# Portier.net
KiCad netlist of a schematic drawn in Altium Designer
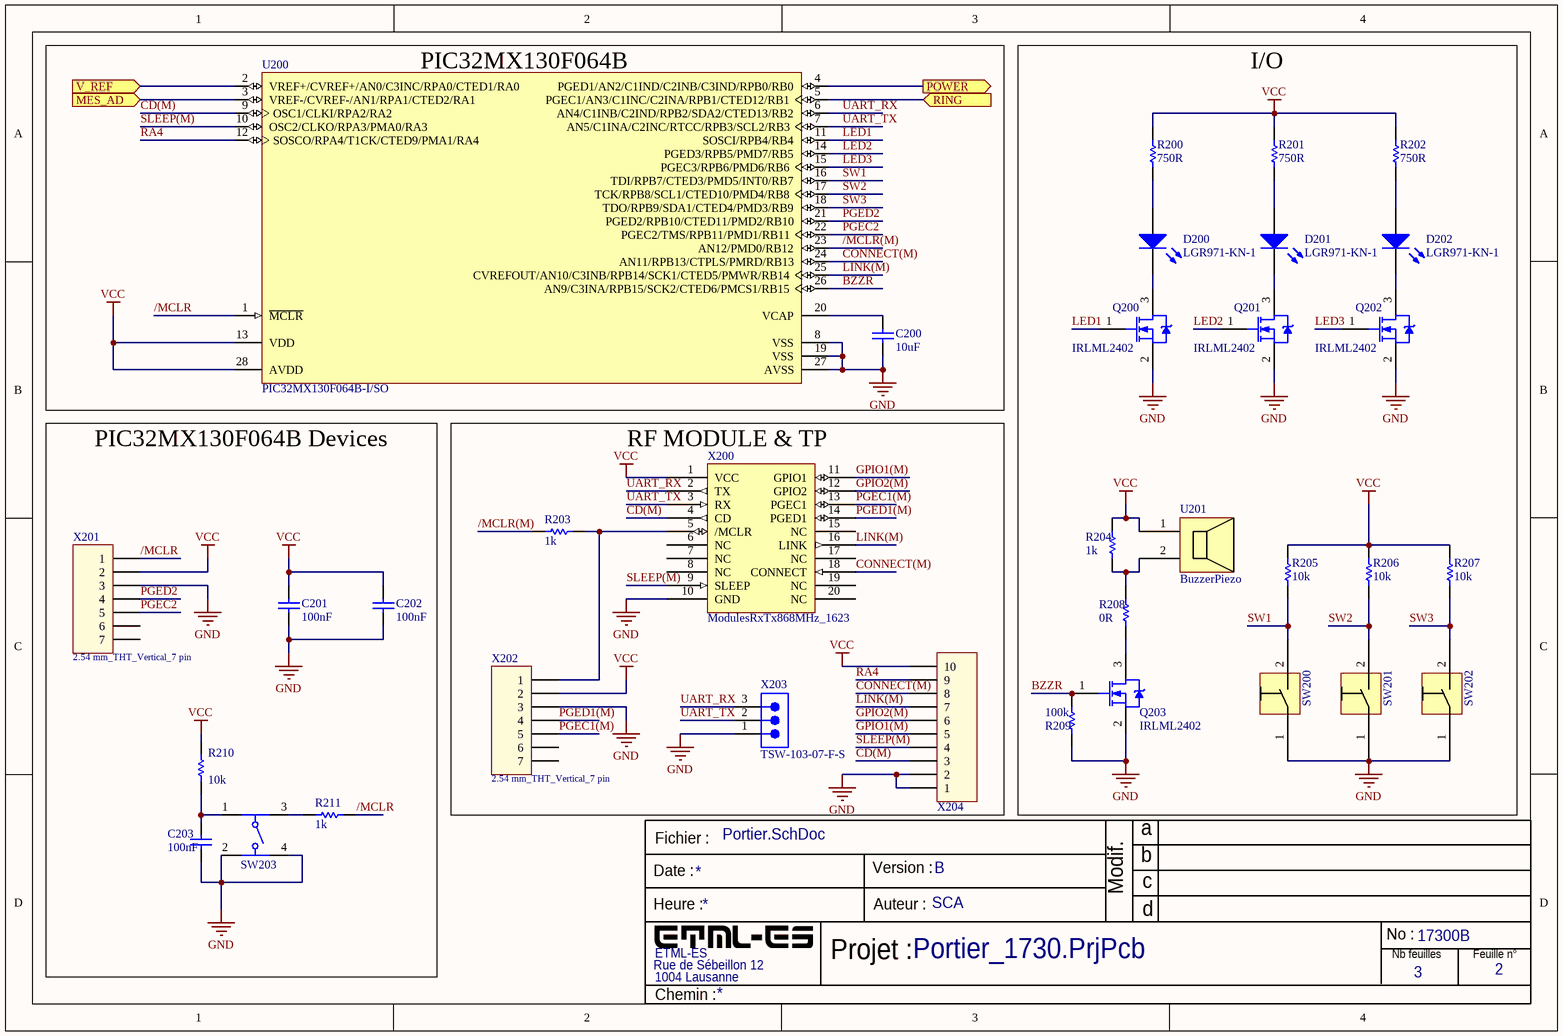
[diagram p0: Portier.SchDoc]

(export (version "E")
  (design (tool "Eeschema 10.0.6"))
  (components
    (comp (ref "C200")
      (value "10uF")
      (footprint "CAPC3216X180X50ML20T25")
      (description "CAP, Ceramic, 10 uF, +/- 10%, 16 V, -55 to 125 degC, 1206 (3216 Metric), RoHS, Tape and Reel")
      (libsource (lib "Altium Content Vault") (part "CMP-1664-00006-1"))
    )
    (comp (ref "C201")
      (value "100nF")
      (footprint "CAPC2013X100X20NL20")
      (description "Chip Capacitor, 100 nF, +/- 10%, 16 V, -55 to 85 degC, 0805 (2012 Metric), RoHS, Tape and Reel")
      (libsource (lib "Altium Content Vault") (part "CMP-1663-00007-1"))
    )
    (comp (ref "C202")
      (value "100nF")
      (footprint "CAPC2013X100X20NL20")
      (description "Chip Capacitor, 100 nF, +/- 10%, 16 V, -55 to 85 degC, 0805 (2012 Metric), RoHS, Tape and Reel")
      (libsource (lib "Altium Content Vault") (part "CMP-1663-00007-1"))
    )
    (comp (ref "C203")
      (value "100nF")
      (footprint "CAPC2013X100X20NL20")
      (description "Chip Capacitor, 100 nF, +/- 10%, 16 V, -55 to 85 degC, 0805 (2012 Metric), RoHS, Tape and Reel")
      (libsource (lib "Altium Content Vault") (part "CMP-1663-00007-1"))
    )
    (comp (ref "D200")
      (value "LGR971-KN-1")
      (footprint "LED_0805")
      (description "SMD mono-color Chip LED, 0805, Green")
      (fields (field (name "MANUFACTURER") "OSRAM"))
      (libsource (lib "KitArmM0") (part "LGR971-KN-1"))
    )
    (comp (ref "D201")
      (value "LGR971-KN-1")
      (footprint "LED_0805")
      (description "SMD mono-color Chip LED, 0805, Green")
      (fields (field (name "MANUFACTURER") "OSRAM"))
      (libsource (lib "KitArmM0") (part "LGR971-KN-1"))
    )
    (comp (ref "D202")
      (value "LGR971-KN-1")
      (footprint "LED_0805")
      (description "SMD mono-color Chip LED, 0805, Green")
      (fields (field (name "MANUFACTURER") "OSRAM"))
      (libsource (lib "KitArmM0") (part "LGR971-KN-1"))
    )
    (comp (ref "Q200")
      (value "IRLML2402")
      (footprint "INTR-IRLML2402TRPBF-3_V")
      (description "HEXFET(R) Power MOSFET, N-Channel, 20 V, 1.2 A, 3-Pin SOT-23, RoHS, Tape and Reel")
      (fields
        (field (name "MANUFACTURER") "Infineon Technologies")
        (field (name "PARTNUMBER") "IRLML2402TRBF")
      )
      (libsource (lib "Altium Content Vault") (part "CMP-2000-05155-1"))
    )
    (comp (ref "Q201")
      (value "IRLML2402")
      (footprint "INTR-IRLML2402TRPBF-3_V")
      (description "HEXFET(R) Power MOSFET, N-Channel, 20 V, 1.2 A, 3-Pin SOT-23, RoHS, Tape and Reel")
      (fields
        (field (name "MANUFACTURER") "Infineon Technologies")
        (field (name "PARTNUMBER") "IRLML2402TRBF")
      )
      (libsource (lib "Altium Content Vault") (part "CMP-2000-05155-1"))
    )
    (comp (ref "Q202")
      (value "IRLML2402")
      (footprint "INTR-IRLML2402TRPBF-3_V")
      (description "HEXFET(R) Power MOSFET, N-Channel, 20 V, 1.2 A, 3-Pin SOT-23, RoHS, Tape and Reel")
      (fields
        (field (name "MANUFACTURER") "Infineon Technologies")
        (field (name "PARTNUMBER") "IRLML2402TRBF")
      )
      (libsource (lib "Altium Content Vault") (part "CMP-2000-05155-1"))
    )
    (comp (ref "Q203")
      (value "IRLML2402")
      (footprint "INTR-IRLML2402TRPBF-3_V")
      (description "HEXFET(R) Power MOSFET, N-Channel, 20 V, 1.2 A, 3-Pin SOT-23, RoHS, Tape and Reel")
      (fields
        (field (name "MANUFACTURER") "Infineon Technologies")
        (field (name "PARTNUMBER") "IRLML2402TRBF")
      )
      (libsource (lib "Altium Content Vault") (part "CMP-2000-05155-1"))
    )
    (comp (ref "R200")
      (value "750R")
      (footprint "RESC0805(2012)_N")
      (description "750R 0.125W 1% 0805 (2012 Metric)  SMD")
      (libsource (lib "Altium Content Vault") (part "CMP-1013-00496-1"))
    )
    (comp (ref "R201")
      (value "750R")
      (footprint "RESC0805(2012)_N")
      (description "750R 0.125W 1% 0805 (2012 Metric)  SMD")
      (libsource (lib "Altium Content Vault") (part "CMP-1013-00496-1"))
    )
    (comp (ref "R202")
      (value "750R")
      (footprint "RESC0805(2012)_N")
      (description "750R 0.125W 1% 0805 (2012 Metric)  SMD")
      (libsource (lib "Altium Content Vault") (part "CMP-1013-00496-1"))
    )
    (comp (ref "R203")
      (value "1k")
      (footprint "RESC2013X60X35ML10T20")
      (description "Chip Resistor, 1 KOhm, +/- 1%, 125 mW, -55 to 155 degC, 0805 (2012 Metric), RoHS, Tape and Reel")
      (libsource (lib "Altium Content Vault") (part "CMP-2100-03671-1"))
    )
    (comp (ref "R204")
      (value "1k")
      (footprint "RESC2013X60X35ML10T20")
      (description "Chip Resistor, 1 KOhm, +/- 1%, 125 mW, -55 to 155 degC, 0805 (2012 Metric), RoHS, Tape and Reel")
      (libsource (lib "Altium Content Vault") (part "CMP-2100-03671-1"))
    )
    (comp (ref "R205")
      (value "10k")
      (footprint "RESC2013X60X35NL10T20")
      (description "Chip Resistor, 10 KOhm, +/- 1%, 0.125 W, -55 to 155 degC, 0805 (2012 Metric), RoHS, Tape and Reel")
      (libsource (lib "Altium Content Vault") (part "RES-2"))
    )
    (comp (ref "R206")
      (value "10k")
      (footprint "RESC2013X60X35NL10T20")
      (description "Chip Resistor, 10 KOhm, +/- 1%, 0.125 W, -55 to 155 degC, 0805 (2012 Metric), RoHS, Tape and Reel")
      (libsource (lib "Altium Content Vault") (part "RES-2"))
    )
    (comp (ref "R207")
      (value "10k")
      (footprint "RESC2013X60X35NL10T20")
      (description "Chip Resistor, 10 KOhm, +/- 1%, 0.125 W, -55 to 155 degC, 0805 (2012 Metric), RoHS, Tape and Reel")
      (libsource (lib "Altium Content Vault") (part "RES-2"))
    )
    (comp (ref "R208")
      (value "0R")
      (footprint "RESC2013X60X35ML10T20")
      (description "Chip Resistor, 1 KOhm, +/- 1%, 125 mW, -55 to 155 degC, 0805 (2012 Metric), RoHS, Tape and Reel")
      (libsource (lib "Altium Content Vault") (part "CMP-2100-03671-1"))
    )
    (comp (ref "R209")
      (value "100k")
      (footprint "RESC2013X60X35ML10T20")
      (description "Chip Resistor, 100 KOhm, +/- 1%, 125 mW, -55 to 155 degC, 0805 (2012 Metric), RoHS, Tape and Reel")
      (libsource (lib "Altium Content Vault") (part "CMP-2100-03671-1"))
    )
    (comp (ref "R210")
      (value "10k")
      (footprint "RESC2013X60X35NL10T20")
      (description "Chip Resistor, 10 KOhm, +/- 1%, 0.125 W, -55 to 155 degC, 0805 (2012 Metric), RoHS, Tape and Reel")
      (libsource (lib "Altium Content Vault") (part "CMP-1659-00011-4"))
    )
    (comp (ref "R211")
      (value "1k")
      (footprint "RESC2013X60X35NL10T20")
      (description "Chip Resistor, 1 KOhm, +/- 1%, 0.125 W, -55 to 155 degC, 0805 (2012 Metric), RoHS, Tape and Reel")
      (libsource (lib "Altium Content Vault") (part "CMP-1659-00011-4"))
    )
    (comp (ref "SW200")
      (value "SW")
      (footprint "Switch_Schurter")
      (description "Switch 12.7x12.7x17.5")
      (fields (field (name "MANUFACTURER") "Schurter"))
      (libsource (lib "CircuitOUT") (part "Switch_Schurter"))
    )
    (comp (ref "SW201")
      (value "SW")
      (footprint "Switch_Schurter")
      (description "Switch 12.7x12.7x17.5")
      (fields (field (name "MANUFACTURER") "Schurter"))
      (libsource (lib "CircuitOUT") (part "Switch_Schurter"))
    )
    (comp (ref "SW202")
      (value "SW")
      (footprint "Switch_Schurter")
      (description "Switch 12.7x12.7x17.5")
      (fields (field (name "MANUFACTURER") "Schurter"))
      (libsource (lib "CircuitOUT") (part "Switch_Schurter"))
    )
    (comp (ref "SW203")
      (value "430152050836")
      (footprint "4301x20508x6_6x6x5")
      (description "WS-TASV 6x6mm Tact Switch, SMD version")
      (fields (field (name "PUBLISHER") "Wurth Elektronik"))
      (libsource (lib "ALTIUM-WS-TASV") (part "430152050836"))
    )
    (comp (ref "U200")
      (value "PIC32MX130F064B-I/SO")
      (footprint "MCHP-SOIC-SO28_L")
      (fields (field (name "MANUFACTURER") "Microchip"))
      (libsource (lib "Altium Content Vault") (part "MCHP-PIC32MX1X0FXXXB-28"))
    )
    (comp (ref "U201")
      (value "BuzzerPiezo")
      (footprint "Buzzer")
      (description "Buzzer 12mm piezo")
      (fields (field (name "MANUFACTURER") "TDK Corporation") (field (name "PARTNUMBER") "PS1240P02BT"))
      (libsource (lib "CircuitOUT") (part "BZR"))
    )
    (comp (ref "X200")
      (value "ModulesRxTx868MHz_1623")
      (footprint "ModulesRxTx868MHz_1623")
      (description "2x Header 2x10 2mm / compatible xBee")
      (libsource (lib "Portier_1730") (part "ModulesRxTx868MHz_1623"))
    )
    (comp (ref "X201")
      (value "2.54 mm_THT_Vertical_7 pin")
      (footprint "61300711121")
      (description "Pin Header WR-PHD, pitch 2.54 mm, THT, Vertical, single row, 7 pin")
      (fields (field (name "PART NUMBER") "61300711121") (field (name "PUBLISHER") "Wurth Elektronik"))
      (libsource (lib "ALTIUM-PHD_2_54_THT_PIN_HEADER_6130XX11121-rev18a") (part "61300711121"))
    )
    (comp (ref "X202")
      (value "2.54 mm_THT_Vertical_7 pin")
      (footprint "61300711121")
      (description "Pin Header WR-PHD, pitch 2.54 mm, THT, Vertical, single row, 7 pin")
      (fields (field (name "PART NUMBER") "61300711121") (field (name "PUBLISHER") "Wurth Elektronik"))
      (libsource (lib "ALTIUM-PHD_2_54_THT_PIN_HEADER_6130XX11121-rev18a") (part "61300711121"))
    )
    (comp (ref "X203")
      (value "TSW-103-07-F-S")
      (footprint "SMTC-TSW-103-07-X-S")
      (description "0.025\" SQ Post Header, Through-hole, Vertical, -55 to 125 degC, 2.54 mm Pitch, 3-Pin, Male, RoHS")
      (libsource (lib "Altium Content Vault") (part "CMP-1024-00331-1"))
    )
    (comp (ref "X204")
      (value "61301011121")
      (footprint "61301011121")
      (description "WR-PHD 2.54 mm THT Pin Header, 10p")
      (fields (field (name "PUBLISHER") "Wurth Elektronik"))
      (libsource (lib "613 0xx 111 21") (part "61301011121"))
    )
  )
  (nets
    (net (code "1") (name "/BZZR") (class "Default")
      (node (ref "Q203") (pin "1") (pinfunction "G_1") (pintype "passive"))
      (node (ref "R209") (pin "2") (pinfunction "2_2") (pintype "passive"))
      (node (ref "U200") (pin "26") (pinfunction "AN9/C3INA/RPB15/SCK2/CTED6/PMCS1/RB15_26") (pintype "bidirectional"))
    )
    (net (code "2") (name "/CD(M)") (class "Default")
      (node (ref "U200") (pin "9") (pinfunction "OSC1/CLKI/RPA2/RA2_9") (pintype "bidirectional"))
      (node (ref "X200") (pin "4") (pinfunction "CD_4") (pintype "output"))
      (node (ref "X204") (pin "3") (pinfunction "3_3") (pintype "passive"))
    )
    (net (code "3") (name "/CONNECT(M)") (class "Default")
      (node (ref "U200") (pin "24") (pinfunction "AN11/RPB13/CTPLS/PMRD/RB13_24") (pintype "bidirectional"))
      (node (ref "X200") (pin "18") (pinfunction "CONNECT_18") (pintype "input"))
      (node (ref "X204") (pin "8") (pinfunction "8_8") (pintype "passive"))
    )
    (net (code "4") (name "/GPIO1(M)") (class "Default")
      (node (ref "X200") (pin "11") (pinfunction "GPIO1_11") (pintype "bidirectional"))
      (node (ref "X204") (pin "5") (pinfunction "5_5") (pintype "passive"))
    )
    (net (code "5") (name "/GPIO2(M)") (class "Default")
      (node (ref "X200") (pin "12") (pinfunction "GPIO2_12") (pintype "bidirectional"))
      (node (ref "X204") (pin "6") (pinfunction "6_6") (pintype "passive"))
    )
    (net (code "6") (name "/LED1") (class "Default")
      (node (ref "Q200") (pin "1") (pinfunction "G_1") (pintype "passive"))
      (node (ref "U200") (pin "11") (pinfunction "SOSCI/RPB4/RB4_11") (pintype "bidirectional"))
    )
    (net (code "7") (name "/LED2") (class "Default")
      (node (ref "Q201") (pin "1") (pinfunction "G_1") (pintype "passive"))
      (node (ref "U200") (pin "14") (pinfunction "PGED3/RPB5/PMD7/RB5_14") (pintype "bidirectional"))
    )
    (net (code "8") (name "/LED3") (class "Default")
      (node (ref "Q202") (pin "1") (pinfunction "G_1") (pintype "passive"))
      (node (ref "U200") (pin "15") (pinfunction "PGEC3/RPB6/PMD6/RB6_15") (pintype "bidirectional"))
    )
    (net (code "9") (name "/LINK(M)") (class "Default")
      (node (ref "U200") (pin "25") (pinfunction "CVREFOUT/AN10/C3INB/RPB14/SCK1/CTED5/PMWR/RB14_25") (pintype "bidirectional"))
      (node (ref "X200") (pin "16") (pinfunction "LINK_16") (pintype "output"))
      (node (ref "X204") (pin "7") (pinfunction "7_7") (pintype "passive"))
    )
    (net (code "10") (name "/MES_AD") (class "Default")
      (node (ref "U200") (pin "3") (pinfunction "VREF-/CVREF-/AN1/RPA1/CTED2/RA1_3") (pintype "bidirectional"))
    )
    (net (code "11") (name "/PGEC1(M)") (class "Default")
      (node (ref "X200") (pin "13") (pinfunction "PGEC1_13") (pintype "bidirectional"))
      (node (ref "X202") (pin "5") (pinfunction "5_5") (pintype "passive"))
    )
    (net (code "12") (name "/PGEC2") (class "Default")
      (node (ref "U200") (pin "22") (pinfunction "PGEC2/TMS/RPB11/PMD1/RB11_22") (pintype "bidirectional"))
      (node (ref "X201") (pin "5") (pinfunction "5_5") (pintype "passive"))
    )
    (net (code "13") (name "/PGED1(M)") (class "Default")
      (node (ref "X200") (pin "14") (pinfunction "PGED1_14") (pintype "bidirectional"))
      (node (ref "X202") (pin "4") (pinfunction "4_4") (pintype "passive"))
    )
    (net (code "14") (name "/PGED2") (class "Default")
      (node (ref "U200") (pin "21") (pinfunction "PGED2/RPB10/CTED11/PMD2/RB10_21") (pintype "bidirectional"))
      (node (ref "X201") (pin "4") (pinfunction "4_4") (pintype "passive"))
    )
    (net (code "15") (name "/POWER") (class "Default")
      (node (ref "U200") (pin "4") (pinfunction "PGED1/AN2/C1IND/C2INB/C3IND/RPB0/RB0_4") (pintype "bidirectional"))
    )
    (net (code "16") (name "/RA4") (class "Default")
      (node (ref "U200") (pin "12") (pinfunction "SOSCO/RPA4/T1CK/CTED9/PMA1/RA4_12") (pintype "bidirectional"))
      (node (ref "X204") (pin "9") (pinfunction "9_9") (pintype "passive"))
    )
    (net (code "17") (name "/RING") (class "Default")
      (node (ref "U200") (pin "5") (pinfunction "PGEC1/AN3/C1INC/C2INA/RPB1/CTED12/RB1_5") (pintype "bidirectional"))
    )
    (net (code "18") (name "/SLEEP(M)") (class "Default")
      (node (ref "U200") (pin "10") (pinfunction "OSC2/CLKO/RPA3/PMA0/RA3_10") (pintype "bidirectional"))
      (node (ref "X200") (pin "9") (pinfunction "SLEEP_9") (pintype "input"))
      (node (ref "X204") (pin "4") (pinfunction "4_4") (pintype "passive"))
    )
    (net (code "19") (name "/SW1") (class "Default")
      (node (ref "R205") (pin "1") (pinfunction "1_1") (pintype "passive"))
      (node (ref "SW200") (pin "2") (pinfunction "2_2") (pintype "passive"))
      (node (ref "U200") (pin "16") (pinfunction "TDI/RPB7/CTED3/PMD5/INT0/RB7_16") (pintype "bidirectional"))
    )
    (net (code "20") (name "/SW2") (class "Default")
      (node (ref "R206") (pin "1") (pinfunction "1_1") (pintype "passive"))
      (node (ref "SW201") (pin "2") (pinfunction "2_2") (pintype "passive"))
      (node (ref "U200") (pin "17") (pinfunction "TCK/RPB8/SCL1/CTED10/PMD4/RB8_17") (pintype "bidirectional"))
    )
    (net (code "21") (name "/SW3") (class "Default")
      (node (ref "R207") (pin "1") (pinfunction "1_1") (pintype "passive"))
      (node (ref "SW202") (pin "2") (pinfunction "2_2") (pintype "passive"))
      (node (ref "U200") (pin "18") (pinfunction "TDO/RPB9/SDA1/CTED4/PMD3/RB9_18") (pintype "bidirectional"))
    )
    (net (code "22") (name "/UART_RX") (class "Default")
      (node (ref "U200") (pin "6") (pinfunction "AN4/C1INB/C2IND/RPB2/SDA2/CTED13/RB2_6") (pintype "bidirectional"))
      (node (ref "X200") (pin "2") (pinfunction "TX_2") (pintype "output"))
      (node (ref "X203") (pin "3") (pinfunction "3_3") (pintype "passive"))
    )
    (net (code "23") (name "/UART_TX") (class "Default")
      (node (ref "U200") (pin "7") (pinfunction "AN5/C1INA/C2INC/RTCC/RPB3/SCL2/RB3_7") (pintype "bidirectional"))
      (node (ref "X200") (pin "3") (pinfunction "RX_3") (pintype "input"))
      (node (ref "X203") (pin "2") (pinfunction "2_2") (pintype "passive"))
    )
    (net (code "24") (name "/V_REF") (class "Default")
      (node (ref "U200") (pin "2") (pinfunction "VREF+/CVREF+/AN0/C3INC/RPA0/CTED1/RA0_2") (pintype "bidirectional"))
    )
    (net (code "25") (name "/{slash}MCLR") (class "Default")
      (node (ref "R211") (pin "2") (pinfunction "2_2") (pintype "passive"))
      (node (ref "U200") (pin "1") (pinfunction "~{MCLR}_1") (pintype "input"))
      (node (ref "X201") (pin "1") (pinfunction "1_1") (pintype "passive"))
    )
    (net (code "26") (name "/{slash}MCLR(M)") (class "Default")
      (node (ref "R203") (pin "2") (pinfunction "2_2") (pintype "passive"))
      (node (ref "U200") (pin "23") (pinfunction "AN12/PMD0/RB12_23") (pintype "bidirectional"))
    )
    (net (code "27") (name "GND") (class "Default")
      (node (ref "C200") (pin "2") (pinfunction "2_2") (pintype "passive"))
      (node (ref "C201") (pin "1") (pinfunction "1_1") (pintype "passive"))
      (node (ref "C202") (pin "1") (pinfunction "1_1") (pintype "passive"))
      (node (ref "C203") (pin "1") (pinfunction "1_1") (pintype "passive"))
      (node (ref "Q200") (pin "2") (pinfunction "S_2") (pintype "passive"))
      (node (ref "Q201") (pin "2") (pinfunction "S_2") (pintype "passive"))
      (node (ref "Q202") (pin "2") (pinfunction "S_2") (pintype "passive"))
      (node (ref "Q203") (pin "2") (pinfunction "S_2") (pintype "passive"))
      (node (ref "R209") (pin "1") (pinfunction "1_1") (pintype "passive"))
      (node (ref "SW200") (pin "1") (pinfunction "1_1") (pintype "passive"))
      (node (ref "SW201") (pin "1") (pinfunction "1_1") (pintype "passive"))
      (node (ref "SW202") (pin "1") (pinfunction "1_1") (pintype "passive"))
      (node (ref "SW203") (pin "2") (pinfunction "2_2") (pintype "passive"))
      (node (ref "SW203") (pin "4") (pinfunction "4_4") (pintype "passive"))
      (node (ref "U200") (pin "19") (pinfunction "VSS_19") (pintype "power_in"))
      (node (ref "U200") (pin "27") (pinfunction "AVSS_27") (pintype "power_in"))
      (node (ref "U200") (pin "8") (pinfunction "VSS_8") (pintype "power_in"))
      (node (ref "X200") (pin "10") (pinfunction "GND_10") (pintype "power_in"))
      (node (ref "X201") (pin "3") (pinfunction "3_3") (pintype "passive"))
      (node (ref "X202") (pin "3") (pinfunction "3_3") (pintype "passive"))
      (node (ref "X203") (pin "1") (pinfunction "1_1") (pintype "passive"))
      (node (ref "X204") (pin "1") (pinfunction "1_1") (pintype "passive"))
      (node (ref "X204") (pin "2") (pinfunction "2_2") (pintype "passive"))
    )
    (net (code "28") (name "Net-(C203-Pad2)") (class "Default")
      (node (ref "C203") (pin "2") (pinfunction "2_2") (pintype "passive"))
      (node (ref "R210") (pin "2") (pinfunction "2_2") (pintype "passive"))
      (node (ref "SW203") (pin "1") (pinfunction "1_1") (pintype "passive"))
    )
    (net (code "29") (name "Net-(D200-A)") (class "Default")
      (node (ref "D200") (pin "1") (pinfunction "A_1") (pintype "passive"))
      (node (ref "R200") (pin "2") (pinfunction "2_2") (pintype "passive"))
    )
    (net (code "30") (name "Net-(D200-K)") (class "Default")
      (node (ref "D200") (pin "2") (pinfunction "K_2") (pintype "passive"))
      (node (ref "Q200") (pin "3") (pinfunction "D_3") (pintype "passive"))
    )
    (net (code "31") (name "Net-(D201-A)") (class "Default")
      (node (ref "D201") (pin "1") (pinfunction "A_1") (pintype "passive"))
      (node (ref "R201") (pin "2") (pinfunction "2_2") (pintype "passive"))
    )
    (net (code "32") (name "Net-(D201-K)") (class "Default")
      (node (ref "D201") (pin "2") (pinfunction "K_2") (pintype "passive"))
      (node (ref "Q201") (pin "3") (pinfunction "D_3") (pintype "passive"))
    )
    (net (code "33") (name "Net-(D202-A)") (class "Default")
      (node (ref "D202") (pin "1") (pinfunction "A_1") (pintype "passive"))
      (node (ref "R202") (pin "1") (pinfunction "1_1") (pintype "passive"))
    )
    (net (code "34") (name "Net-(D202-K)") (class "Default")
      (node (ref "D202") (pin "2") (pinfunction "K_2") (pintype "passive"))
      (node (ref "Q202") (pin "3") (pinfunction "D_3") (pintype "passive"))
    )
    (net (code "35") (name "Net-(Q203-D)") (class "Default")
      (node (ref "Q203") (pin "3") (pinfunction "D_3") (pintype "passive"))
      (node (ref "R208") (pin "1") (pinfunction "1_1") (pintype "passive"))
    )
    (net (code "36") (name "Net-(R204-Pad1)") (class "Default")
      (node (ref "R204") (pin "1") (pinfunction "1_1") (pintype "passive"))
      (node (ref "R208") (pin "2") (pinfunction "2_2") (pintype "passive"))
      (node (ref "U201") (pin "2") (pintype "passive"))
    )
    (net (code "37") (name "Net-(R211-Pad1)") (class "Default")
      (node (ref "R211") (pin "1") (pinfunction "1_1") (pintype "passive"))
      (node (ref "SW203") (pin "3") (pinfunction "3_3") (pintype "passive"))
    )
    (net (code "38") (name "Net-(U200-VCAP)") (class "Default")
      (node (ref "C200") (pin "1") (pinfunction "1_1") (pintype "passive"))
      (node (ref "U200") (pin "20") (pinfunction "VCAP_20") (pintype "passive"))
    )
    (net (code "39") (name "Net-(X200-{slash}MCLR)") (class "Default")
      (node (ref "R203") (pin "1") (pinfunction "1_1") (pintype "passive"))
      (node (ref "X200") (pin "5") (pinfunction "/MCLR_5") (pintype "bidirectional"))
      (node (ref "X202") (pin "1") (pinfunction "1_1") (pintype "passive"))
    )
    (net (code "40") (name "VCC") (class "Default")
      (node (ref "C201") (pin "2") (pinfunction "2_2") (pintype "passive"))
      (node (ref "C202") (pin "2") (pinfunction "2_2") (pintype "passive"))
      (node (ref "R200") (pin "1") (pinfunction "1_1") (pintype "passive"))
      (node (ref "R201") (pin "1") (pinfunction "1_1") (pintype "passive"))
      (node (ref "R202") (pin "2") (pinfunction "2_2") (pintype "passive"))
      (node (ref "R204") (pin "2") (pinfunction "2_2") (pintype "passive"))
      (node (ref "R205") (pin "2") (pinfunction "2_2") (pintype "passive"))
      (node (ref "R206") (pin "2") (pinfunction "2_2") (pintype "passive"))
      (node (ref "R207") (pin "2") (pinfunction "2_2") (pintype "passive"))
      (node (ref "R210") (pin "1") (pinfunction "1_1") (pintype "passive"))
      (node (ref "U200") (pin "13") (pinfunction "VDD_13") (pintype "power_in"))
      (node (ref "U200") (pin "28") (pinfunction "AVDD_28") (pintype "power_in"))
      (node (ref "U201") (pin "1") (pintype "passive"))
      (node (ref "X200") (pin "1") (pinfunction "VCC_1") (pintype "power_in"))
      (node (ref "X201") (pin "2") (pinfunction "2_2") (pintype "passive"))
      (node (ref "X202") (pin "2") (pinfunction "2_2") (pintype "passive"))
      (node (ref "X204") (pin "10") (pinfunction "10_10") (pintype "passive"))
    )
    (net (code "41") (name "unconnected-(X200-NC-Pad6)") (class "Default")
      (node (ref "X200") (pin "6") (pinfunction "NC_6") (pintype "passive"))
    )
    (net (code "42") (name "unconnected-(X200-NC-Pad7)") (class "Default")
      (node (ref "X200") (pin "7") (pinfunction "NC_7") (pintype "passive"))
    )
    (net (code "43") (name "unconnected-(X200-NC-Pad8)") (class "Default")
      (node (ref "X200") (pin "8") (pinfunction "NC_8") (pintype "passive"))
    )
    (net (code "44") (name "unconnected-(X200-NC-Pad15)") (class "Default")
      (node (ref "X200") (pin "15") (pinfunction "NC_15") (pintype "passive"))
    )
    (net (code "45") (name "unconnected-(X200-NC-Pad17)") (class "Default")
      (node (ref "X200") (pin "17") (pinfunction "NC_17") (pintype "passive"))
    )
    (net (code "46") (name "unconnected-(X200-NC-Pad19)") (class "Default")
      (node (ref "X200") (pin "19") (pinfunction "NC_19") (pintype "passive"))
    )
    (net (code "47") (name "unconnected-(X200-NC-Pad20)") (class "Default")
      (node (ref "X200") (pin "20") (pinfunction "NC_20") (pintype "passive"))
    )
    (net (code "48") (name "unconnected-(X201-Pad6)") (class "Default")
      (node (ref "X201") (pin "6") (pinfunction "6_6") (pintype "passive"))
    )
    (net (code "49") (name "unconnected-(X201-Pad7)") (class "Default")
      (node (ref "X201") (pin "7") (pinfunction "7_7") (pintype "passive"))
    )
    (net (code "50") (name "unconnected-(X202-Pad6)") (class "Default")
      (node (ref "X202") (pin "6") (pinfunction "6_6") (pintype "passive"))
    )
    (net (code "51") (name "unconnected-(X202-Pad7)") (class "Default")
      (node (ref "X202") (pin "7") (pinfunction "7_7") (pintype "passive"))
    )
  )
)
